# remoteVolume.net
KiCad netlist of a schematic drawn in EAGLE
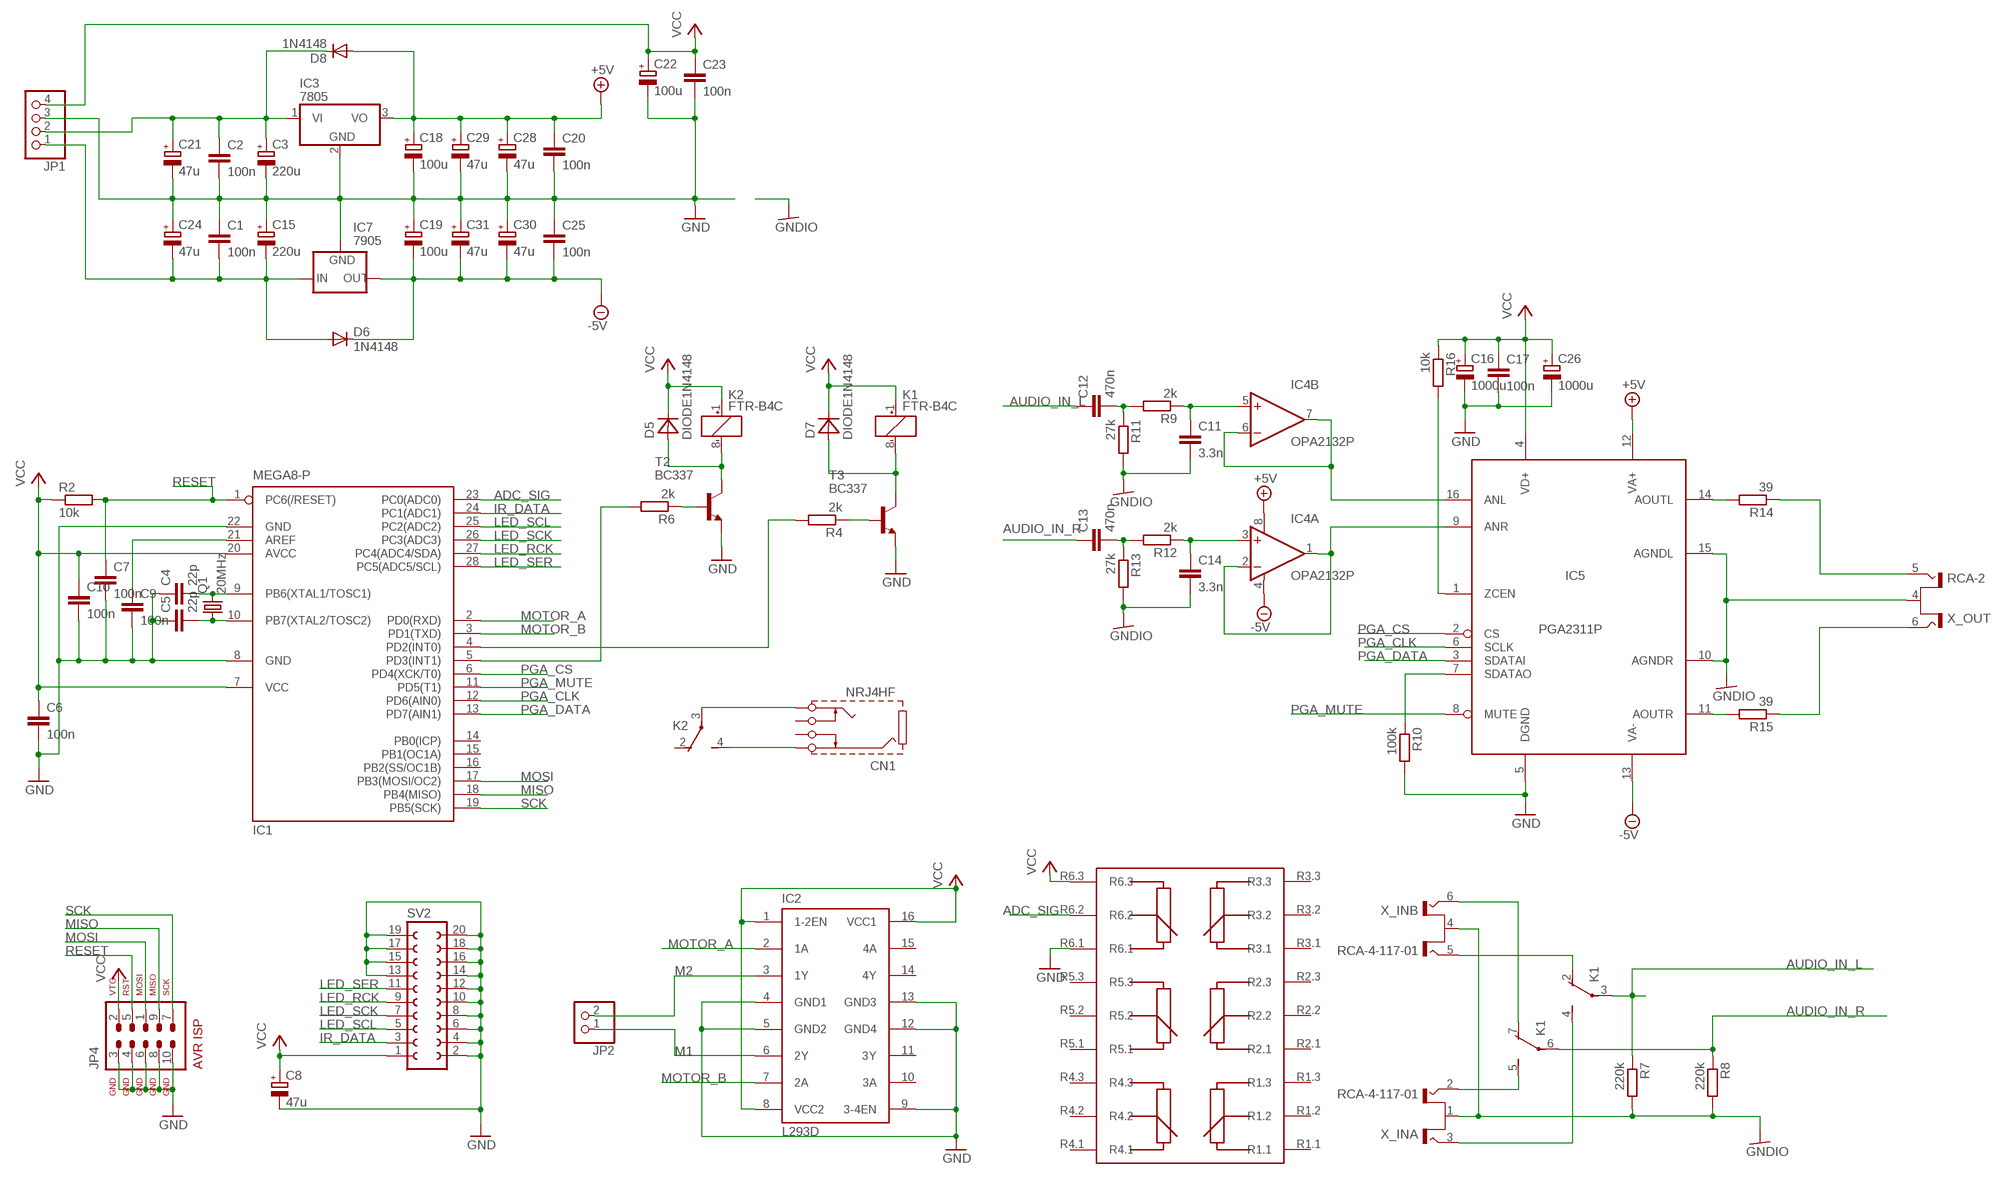
[diagram p0: schematic, sheet 1]

(export (version "E")
  (design (tool "Eeschema 10.0.6"))
  (components
    (comp (ref "C1")
      (value "100n")
      (footprint "eagle-import:C025-025X050")
      (libsource (lib "eagle-import") (part "C-EU025-025X050"))
    )
    (comp (ref "C2")
      (value "100n")
      (footprint "eagle-import:C025-025X050")
      (libsource (lib "eagle-import") (part "C-EU025-025X050"))
    )
    (comp (ref "C3")
      (value "220u")
      (footprint "eagle-import:E2,5-6")
      (libsource (lib "eagle-import") (part "CPOL-EUE2.5-6"))
    )
    (comp (ref "C4")
      (value "22p")
      (footprint "eagle-import:C025-025X050")
      (libsource (lib "eagle-import") (part "C-EU025-025X050"))
    )
    (comp (ref "C5")
      (value "22p")
      (footprint "eagle-import:C025-025X050")
      (libsource (lib "eagle-import") (part "C-EU025-025X050"))
    )
    (comp (ref "C6")
      (value "100n")
      (footprint "eagle-import:C025-025X050")
      (libsource (lib "eagle-import") (part "C-EU025-025X050"))
    )
    (comp (ref "C7")
      (value "100n")
      (footprint "eagle-import:C025-025X050")
      (libsource (lib "eagle-import") (part "C-EU025-025X050"))
    )
    (comp (ref "C8")
      (value "47u")
      (footprint "eagle-import:E2,5-6")
      (libsource (lib "eagle-import") (part "CPOL-EUE2.5-6"))
    )
    (comp (ref "C9")
      (value "100n")
      (footprint "eagle-import:C025-025X050")
      (libsource (lib "eagle-import") (part "C-EU025-025X050"))
    )
    (comp (ref "C10")
      (value "100n")
      (footprint "eagle-import:C025-025X050")
      (libsource (lib "eagle-import") (part "C-EU025-025X050"))
    )
    (comp (ref "C11")
      (value "3.3n")
      (footprint "eagle-import:C050-055X075")
      (libsource (lib "eagle-import") (part "C-EU050-055X075"))
    )
    (comp (ref "C12")
      (value "470n")
      (footprint "eagle-import:C5B3.5")
      (libsource (lib "eagle-import") (part "C5/3.5"))
    )
    (comp (ref "C13")
      (value "470n")
      (footprint "eagle-import:C5B3.5")
      (libsource (lib "eagle-import") (part "C5/3.5"))
    )
    (comp (ref "C14")
      (value "3.3n")
      (footprint "eagle-import:C050-055X075")
      (libsource (lib "eagle-import") (part "C-EU050-055X075"))
    )
    (comp (ref "C15")
      (value "220u")
      (footprint "eagle-import:E2,5-6")
      (libsource (lib "eagle-import") (part "CPOL-EUE2.5-6"))
    )
    (comp (ref "C16")
      (value "1000u")
      (footprint "eagle-import:E3,5-8")
      (libsource (lib "eagle-import") (part "CPOL-EUE3.5-8"))
    )
    (comp (ref "C17")
      (value "100n")
      (footprint "eagle-import:C025-025X050")
      (libsource (lib "eagle-import") (part "C-EU025-025X050"))
    )
    (comp (ref "C18")
      (value "100u")
      (footprint "eagle-import:E2,5-5")
      (libsource (lib "eagle-import") (part "CPOL-EUE2.5-5"))
    )
    (comp (ref "C19")
      (value "100u")
      (footprint "eagle-import:E2,5-5")
      (libsource (lib "eagle-import") (part "CPOL-EUE2.5-5"))
    )
    (comp (ref "C20")
      (value "100n")
      (footprint "eagle-import:C025-025X050")
      (libsource (lib "eagle-import") (part "C-EU025-025X050"))
    )
    (comp (ref "C21")
      (value "47u")
      (footprint "eagle-import:E2,5-5")
      (libsource (lib "eagle-import") (part "CPOL-EUE2.5-5"))
    )
    (comp (ref "C22")
      (value "100u")
      (footprint "eagle-import:E2,5-5")
      (libsource (lib "eagle-import") (part "CPOL-EUE2.5-5"))
    )
    (comp (ref "C23")
      (value "100n")
      (footprint "eagle-import:C025-025X050")
      (libsource (lib "eagle-import") (part "C-EU025-025X050"))
    )
    (comp (ref "C24")
      (value "47u")
      (footprint "eagle-import:E2,5-5")
      (libsource (lib "eagle-import") (part "CPOL-EUE2.5-5"))
    )
    (comp (ref "C25")
      (value "100n")
      (footprint "eagle-import:C025-025X050")
      (libsource (lib "eagle-import") (part "C-EU025-025X050"))
    )
    (comp (ref "C26")
      (value "1000u")
      (footprint "eagle-import:E3,5-8")
      (libsource (lib "eagle-import") (part "CPOL-EUE3.5-8"))
    )
    (comp (ref "C28")
      (value "47u")
      (footprint "eagle-import:E2,5-5")
      (libsource (lib "eagle-import") (part "CPOL-EUE2.5-5"))
    )
    (comp (ref "C29")
      (value "47u")
      (footprint "eagle-import:E2,5-5")
      (libsource (lib "eagle-import") (part "CPOL-EUE2.5-5"))
    )
    (comp (ref "C30")
      (value "47u")
      (footprint "eagle-import:E2,5-5")
      (libsource (lib "eagle-import") (part "CPOL-EUE2.5-5"))
    )
    (comp (ref "C31")
      (value "47u")
      (footprint "eagle-import:E2,5-5")
      (libsource (lib "eagle-import") (part "CPOL-EUE2.5-5"))
    )
    (comp (ref "CN1")
      (value "NRJ4HF")
      (footprint "eagle-import:NRJ4HF")
      (libsource (lib "eagle-import") (part "NRJ4HF"))
    )
    (comp (ref "D5")
      (value "DIODE1N4148")
      (footprint "eagle-import:DO-35")
      (libsource (lib "eagle-import") (part "DIODE1N4148"))
    )
    (comp (ref "D6")
      (value "1N4148")
      (footprint "eagle-import:DO35-7")
      (libsource (lib "eagle-import") (part "1N4148DO35-7"))
    )
    (comp (ref "D7")
      (value "DIODE1N4148")
      (footprint "eagle-import:DO-35")
      (libsource (lib "eagle-import") (part "DIODE1N4148"))
    )
    (comp (ref "D8")
      (value "1N4148")
      (footprint "eagle-import:DO35-7")
      (libsource (lib "eagle-import") (part "1N4148DO35-7"))
    )
    (comp (ref "IC1")
      (value "MEGA8-P")
      (footprint "eagle-import:DIL28-3")
      (libsource (lib "eagle-import") (part "MEGA8-P"))
    )
    (comp (ref "IC2")
      (value "L293D")
      (footprint "eagle-import:DIL16")
      (libsource (lib "eagle-import") (part "L293D"))
    )
    (comp (ref "IC3")
      (value "7805")
      (footprint "eagle-import:TO220V")
      (libsource (lib "eagle-import") (part "78TV05"))
    )
    (comp (ref "IC4")
      (value "OPA2132P")
      (footprint "eagle-import:DIL08")
      (libsource (lib "eagle-import") (part "OPA2132P"))
    )
    (comp (ref "IC5")
      (value "PGA2311P")
      (footprint "eagle-import:DIL16")
      (libsource (lib "eagle-import") (part "PGA2311P"))
    )
    (comp (ref "IC7")
      (value "7905")
      (footprint "eagle-import:79XXS")
      (libsource (lib "eagle-import") (part "79XXS"))
    )
    (comp (ref "JP1")
      (value "PINHD-1X4/90")
      (footprint "eagle-import:1X04_90")
      (libsource (lib "eagle-import") (part "PINHD-1X4/90"))
    )
    (comp (ref "JP2")
      (value "PINHD-1X2")
      (footprint "eagle-import:1X02")
      (libsource (lib "eagle-import") (part "PINHD-1X2"))
    )
    (comp (ref "JP4")
      (value "AVR-ISP-10")
      (footprint "eagle-import:AVR-ISP-10")
      (libsource (lib "eagle-import") (part "AVR-ISP-10"))
    )
    (comp (ref "K1")
      (value "FTR-B4C")
      (footprint "eagle-import:FTR-B4C")
      (libsource (lib "eagle-import") (part "FTR-B4C"))
    )
    (comp (ref "K2")
      (value "FTR-B4C")
      (footprint "eagle-import:FTR-B4C")
      (libsource (lib "eagle-import") (part "FTR-B4C"))
    )
    (comp (ref "Q1")
      (value "20MHz")
      (footprint "eagle-import:HC49_S")
      (libsource (lib "eagle-import") (part "CRYSTALHC49S"))
    )
    (comp (ref "R2")
      (value "10k")
      (footprint "eagle-import:0207_7")
      (libsource (lib "eagle-import") (part "R-EU_0207/7"))
    )
    (comp (ref "R4")
      (value "2k")
      (footprint "eagle-import:0207_7")
      (libsource (lib "eagle-import") (part "R-EU_0207/7"))
    )
    (comp (ref "R6")
      (value "2k")
      (footprint "eagle-import:0207_7")
      (libsource (lib "eagle-import") (part "R-EU_0207/7"))
    )
    (comp (ref "R7")
      (value "220k")
      (footprint "eagle-import:0207_7")
      (libsource (lib "eagle-import") (part "R-EU_0207/7"))
    )
    (comp (ref "R8")
      (value "220k")
      (footprint "eagle-import:0207_7")
      (libsource (lib "eagle-import") (part "R-EU_0207/7"))
    )
    (comp (ref "R9")
      (value "2k")
      (footprint "eagle-import:0207_7")
      (libsource (lib "eagle-import") (part "R-EU_0207/7"))
    )
    (comp (ref "R10")
      (value "100k")
      (footprint "eagle-import:0207_7")
      (libsource (lib "eagle-import") (part "R-EU_0207/7"))
    )
    (comp (ref "R11")
      (value "27k")
      (footprint "eagle-import:0207_7")
      (libsource (lib "eagle-import") (part "R-EU_0207/7"))
    )
    (comp (ref "R12")
      (value "2k")
      (footprint "eagle-import:0207_7")
      (libsource (lib "eagle-import") (part "R-EU_0207/7"))
    )
    (comp (ref "R13")
      (value "27k")
      (footprint "eagle-import:0207_7")
      (libsource (lib "eagle-import") (part "R-EU_0207/7"))
    )
    (comp (ref "R14")
      (value "39")
      (footprint "eagle-import:0207_7")
      (libsource (lib "eagle-import") (part "R-EU_0207/7"))
    )
    (comp (ref "R15")
      (value "39")
      (footprint "eagle-import:0207_7")
      (libsource (lib "eagle-import") (part "R-EU_0207/7"))
    )
    (comp (ref "R16")
      (value "10k")
      (footprint "eagle-import:0207_7")
      (libsource (lib "eagle-import") (part "R-EU_0207/7"))
    )
    (comp (ref "SV2")
      (value "FE10-2W")
      (footprint "eagle-import:FE10-2W")
      (libsource (lib "eagle-import") (part "FE10-2W"))
    )
    (comp (ref "T2")
      (value "BC337")
      (footprint "eagle-import:TO92")
      (libsource (lib "eagle-import") (part "BC337"))
    )
    (comp (ref "T3")
      (value "BC337")
      (footprint "eagle-import:TO92")
      (libsource (lib "eagle-import") (part "BC337"))
    )
    (comp (ref "U$1")
      (value "RK16816MG")
      (footprint "eagle-import:RK16816MG")
      (libsource (lib "eagle-import") (part "RK16816MG"))
    )
    (comp (ref "X_IN")
      (value "RCA-4-117-01")
      (footprint "eagle-import:RCA-4-117-01")
      (libsource (lib "eagle-import") (part "RCA-4-117-01"))
    )
    (comp (ref "X_OUT")
      (value "RCA-2")
      (footprint "eagle-import:RCA-2")
      (libsource (lib "eagle-import") (part "RCA-2"))
    )
  )
  (nets
    (net (code "1") (name "+5V") (class "Default")
      (node (ref "C18") (pin "+") (pinfunction "+_+") (pintype "passive"))
      (node (ref "C20") (pin "1") (pinfunction "1_1") (pintype "passive"))
      (node (ref "C28") (pin "+") (pinfunction "+_+") (pintype "passive"))
      (node (ref "C29") (pin "+") (pinfunction "+_+") (pintype "passive"))
      (node (ref "D8") (pin "A") (pinfunction "A_A") (pintype "passive"))
      (node (ref "IC3") (pin "3") (pinfunction "VO_3") (pintype "passive"))
      (node (ref "IC4") (pin "8") (pinfunction "V+_8") (pintype "power_in"))
      (node (ref "IC5") (pin "12") (pinfunction "VA+_12") (pintype "power_in"))
    )
    (net (code "2") (name "-5V") (class "Default")
      (node (ref "C19") (pin "-") (pinfunction "-_-") (pintype "passive"))
      (node (ref "C25") (pin "2") (pinfunction "2_2") (pintype "passive"))
      (node (ref "C30") (pin "-") (pinfunction "-_-") (pintype "passive"))
      (node (ref "C31") (pin "-") (pinfunction "-_-") (pintype "passive"))
      (node (ref "D6") (pin "C") (pinfunction "C_C") (pintype "passive"))
      (node (ref "IC4") (pin "4") (pinfunction "V-_4") (pintype "power_in"))
      (node (ref "IC5") (pin "13") (pinfunction "VA-_13") (pintype "power_in"))
      (node (ref "IC7") (pin "OUT") (pinfunction "OUT_OUT") (pintype "passive"))
    )
    (net (code "3") (name "/ADC_SIG") (class "Default")
      (node (ref "IC1") (pin "23") (pinfunction "PC0(ADC0)_23") (pintype "bidirectional"))
      (node (ref "U$1") (pin "R6.2") (pinfunction "R6.2_R6.2") (pintype "bidirectional"))
    )
    (net (code "4") (name "/AUDIO_IN_L") (class "Default")
      (node (ref "C12") (pin "1") (pinfunction "1_1") (pintype "passive"))
      (node (ref "K1") (pin "3") (pinfunction "P_3") (pintype "passive"))
      (node (ref "R7") (pin "1") (pinfunction "1_1") (pintype "passive"))
    )
    (net (code "5") (name "/AUDIO_IN_R") (class "Default")
      (node (ref "C13") (pin "1") (pinfunction "1_1") (pintype "passive"))
      (node (ref "K1") (pin "6") (pinfunction "P_6") (pintype "passive"))
      (node (ref "R8") (pin "1") (pinfunction "1_1") (pintype "passive"))
    )
    (net (code "6") (name "/IR_DATA") (class "Default")
      (node (ref "IC1") (pin "24") (pinfunction "PC1(ADC1)_24") (pintype "bidirectional"))
      (node (ref "SV2") (pin "3") (pinfunction "3_3") (pintype "passive"))
    )
    (net (code "7") (name "/LED_RCK") (class "Default")
      (node (ref "IC1") (pin "27") (pinfunction "PC4(ADC4/SDA)_27") (pintype "bidirectional"))
      (node (ref "SV2") (pin "9") (pinfunction "9_9") (pintype "passive"))
    )
    (net (code "8") (name "/LED_SCK") (class "Default")
      (node (ref "IC1") (pin "26") (pinfunction "PC3(ADC3)_26") (pintype "bidirectional"))
      (node (ref "SV2") (pin "7") (pinfunction "7_7") (pintype "passive"))
    )
    (net (code "9") (name "/LED_SCL") (class "Default")
      (node (ref "IC1") (pin "25") (pinfunction "PC2(ADC2)_25") (pintype "bidirectional"))
      (node (ref "SV2") (pin "5") (pinfunction "5_5") (pintype "passive"))
    )
    (net (code "10") (name "/LED_SER") (class "Default")
      (node (ref "IC1") (pin "28") (pinfunction "PC5(ADC5/SCL)_28") (pintype "bidirectional"))
      (node (ref "SV2") (pin "11") (pinfunction "11_11") (pintype "passive"))
    )
    (net (code "11") (name "/M1") (class "Default")
      (node (ref "IC2") (pin "6") (pinfunction "2Y_6") (pintype "output"))
      (node (ref "JP2") (pin "1") (pinfunction "1_1") (pintype "passive"))
    )
    (net (code "12") (name "/M2") (class "Default")
      (node (ref "IC2") (pin "3") (pinfunction "1Y_3") (pintype "output"))
      (node (ref "JP2") (pin "2") (pinfunction "2_2") (pintype "passive"))
    )
    (net (code "13") (name "/MISO") (class "Default")
      (node (ref "IC1") (pin "18") (pinfunction "PB4(MISO)_18") (pintype "bidirectional"))
      (node (ref "JP4") (pin "9") (pinfunction "9_9") (pintype "passive"))
    )
    (net (code "14") (name "/MOSI") (class "Default")
      (node (ref "IC1") (pin "17") (pinfunction "PB3(MOSI/OC2)_17") (pintype "bidirectional"))
      (node (ref "JP4") (pin "1") (pinfunction "1_1") (pintype "passive"))
    )
    (net (code "15") (name "/MOTOR_A") (class "Default")
      (node (ref "IC1") (pin "2") (pinfunction "PD0(RXD)_2") (pintype "bidirectional"))
      (node (ref "IC2") (pin "2") (pinfunction "1A_2") (pintype "input"))
    )
    (net (code "16") (name "/MOTOR_B") (class "Default")
      (node (ref "IC1") (pin "3") (pinfunction "PD1(TXD)_3") (pintype "bidirectional"))
      (node (ref "IC2") (pin "7") (pinfunction "2A_7") (pintype "input"))
    )
    (net (code "17") (name "/PGA_CLK") (class "Default")
      (node (ref "IC1") (pin "12") (pinfunction "PD6(AIN0)_12") (pintype "bidirectional"))
      (node (ref "IC5") (pin "6") (pinfunction "SCLK_6") (pintype "input"))
    )
    (net (code "18") (name "/PGA_CS") (class "Default")
      (node (ref "IC1") (pin "6") (pinfunction "PD4(XCK/T0)_6") (pintype "bidirectional"))
      (node (ref "IC5") (pin "2") (pinfunction "CS_2") (pintype "input"))
    )
    (net (code "19") (name "/PGA_DATA") (class "Default")
      (node (ref "IC1") (pin "13") (pinfunction "PD7(AIN1)_13") (pintype "bidirectional"))
      (node (ref "IC5") (pin "3") (pinfunction "SDATAI_3") (pintype "input"))
    )
    (net (code "20") (name "/PGA_MUTE") (class "Default")
      (node (ref "IC1") (pin "11") (pinfunction "PD5(T1)_11") (pintype "bidirectional"))
      (node (ref "IC5") (pin "8") (pinfunction "MUTE_8") (pintype "input"))
    )
    (net (code "21") (name "/RESET") (class "Default")
      (node (ref "C7") (pin "1") (pinfunction "1_1") (pintype "passive"))
      (node (ref "IC1") (pin "1") (pinfunction "PC6(/RESET)_1") (pintype "bidirectional"))
      (node (ref "JP4") (pin "5") (pinfunction "5_5") (pintype "passive"))
      (node (ref "R2") (pin "2") (pinfunction "2_2") (pintype "passive"))
    )
    (net (code "22") (name "/SCK") (class "Default")
      (node (ref "IC1") (pin "19") (pinfunction "PB5(SCK)_19") (pintype "bidirectional"))
      (node (ref "JP4") (pin "7") (pinfunction "7_7") (pintype "passive"))
    )
    (net (code "23") (name "GND") (class "Default")
      (node (ref "C1") (pin "1") (pinfunction "1_1") (pintype "passive"))
      (node (ref "C10") (pin "2") (pinfunction "2_2") (pintype "passive"))
      (node (ref "C15") (pin "+") (pinfunction "+_+") (pintype "passive"))
      (node (ref "C16") (pin "-") (pinfunction "-_-") (pintype "passive"))
      (node (ref "C17") (pin "2") (pinfunction "2_2") (pintype "passive"))
      (node (ref "C18") (pin "-") (pinfunction "-_-") (pintype "passive"))
      (node (ref "C19") (pin "+") (pinfunction "+_+") (pintype "passive"))
      (node (ref "C2") (pin "2") (pinfunction "2_2") (pintype "passive"))
      (node (ref "C20") (pin "2") (pinfunction "2_2") (pintype "passive"))
      (node (ref "C21") (pin "-") (pinfunction "-_-") (pintype "passive"))
      (node (ref "C22") (pin "-") (pinfunction "-_-") (pintype "passive"))
      (node (ref "C23") (pin "2") (pinfunction "2_2") (pintype "passive"))
      (node (ref "C24") (pin "+") (pinfunction "+_+") (pintype "passive"))
      (node (ref "C25") (pin "1") (pinfunction "1_1") (pintype "passive"))
      (node (ref "C26") (pin "-") (pinfunction "-_-") (pintype "passive"))
      (node (ref "C28") (pin "-") (pinfunction "-_-") (pintype "passive"))
      (node (ref "C29") (pin "-") (pinfunction "-_-") (pintype "passive"))
      (node (ref "C3") (pin "-") (pinfunction "-_-") (pintype "passive"))
      (node (ref "C30") (pin "+") (pinfunction "+_+") (pintype "passive"))
      (node (ref "C31") (pin "+") (pinfunction "+_+") (pintype "passive"))
      (node (ref "C4") (pin "1") (pinfunction "1_1") (pintype "passive"))
      (node (ref "C5") (pin "1") (pinfunction "1_1") (pintype "passive"))
      (node (ref "C6") (pin "2") (pinfunction "2_2") (pintype "passive"))
      (node (ref "C7") (pin "2") (pinfunction "2_2") (pintype "passive"))
      (node (ref "C8") (pin "-") (pinfunction "-_-") (pintype "passive"))
      (node (ref "C9") (pin "2") (pinfunction "2_2") (pintype "passive"))
      (node (ref "IC1") (pin "22") (pinfunction "GND_22") (pintype "power_in"))
      (node (ref "IC1") (pin "8") (pinfunction "GND_8") (pintype "power_in"))
      (node (ref "IC2") (pin "12") (pinfunction "GND4_12") (pintype "power_in"))
      (node (ref "IC2") (pin "13") (pinfunction "GND3_13") (pintype "power_in"))
      (node (ref "IC2") (pin "4") (pinfunction "GND1_4") (pintype "power_in"))
      (node (ref "IC2") (pin "5") (pinfunction "GND2_5") (pintype "power_in"))
      (node (ref "IC2") (pin "9") (pinfunction "3-4EN_9") (pintype "input"))
      (node (ref "IC3") (pin "2") (pinfunction "GND_2") (pintype "passive"))
      (node (ref "IC5") (pin "5") (pinfunction "DGND_5") (pintype "power_in"))
      (node (ref "IC7") (pin "GND") (pinfunction "GND_GND") (pintype "input"))
      (node (ref "JP1") (pin "3") (pinfunction "3_3") (pintype "passive"))
      (node (ref "JP4") (pin "10") (pinfunction "10_10") (pintype "passive"))
      (node (ref "JP4") (pin "3") (pinfunction "3_3") (pintype "passive"))
      (node (ref "JP4") (pin "4") (pinfunction "4_4") (pintype "passive"))
      (node (ref "JP4") (pin "6") (pinfunction "6_6") (pintype "passive"))
      (node (ref "JP4") (pin "8") (pinfunction "8_8") (pintype "passive"))
      (node (ref "R10") (pin "2") (pinfunction "2_2") (pintype "passive"))
      (node (ref "SV2") (pin "10") (pinfunction "10_10") (pintype "passive"))
      (node (ref "SV2") (pin "12") (pinfunction "12_12") (pintype "passive"))
      (node (ref "SV2") (pin "13") (pinfunction "13_13") (pintype "passive"))
      (node (ref "SV2") (pin "14") (pinfunction "14_14") (pintype "passive"))
      (node (ref "SV2") (pin "15") (pinfunction "15_15") (pintype "passive"))
      (node (ref "SV2") (pin "16") (pinfunction "16_16") (pintype "passive"))
      (node (ref "SV2") (pin "17") (pinfunction "17_17") (pintype "passive"))
      (node (ref "SV2") (pin "18") (pinfunction "18_18") (pintype "passive"))
      (node (ref "SV2") (pin "19") (pinfunction "19_19") (pintype "passive"))
      (node (ref "SV2") (pin "2") (pinfunction "2_2") (pintype "passive"))
      (node (ref "SV2") (pin "20") (pinfunction "20_20") (pintype "passive"))
      (node (ref "SV2") (pin "4") (pinfunction "4_4") (pintype "passive"))
      (node (ref "SV2") (pin "6") (pinfunction "6_6") (pintype "passive"))
      (node (ref "SV2") (pin "8") (pinfunction "8_8") (pintype "passive"))
      (node (ref "T2") (pin "1") (pinfunction "E_1") (pintype "passive"))
      (node (ref "T3") (pin "1") (pinfunction "E_1") (pintype "passive"))
      (node (ref "U$1") (pin "R6.1") (pinfunction "R6.1_R6.1") (pintype "bidirectional"))
    )
    (net (code "24") (name "GNDIO") (class "Default")
      (node (ref "C11") (pin "2") (pinfunction "2_2") (pintype "passive"))
      (node (ref "C14") (pin "2") (pinfunction "2_2") (pintype "passive"))
      (node (ref "IC5") (pin "10") (pinfunction "AGNDR_10") (pintype "power_in"))
      (node (ref "IC5") (pin "15") (pinfunction "AGNDL_15") (pintype "power_in"))
      (node (ref "R11") (pin "2") (pinfunction "2_2") (pintype "passive"))
      (node (ref "R13") (pin "2") (pinfunction "2_2") (pintype "passive"))
      (node (ref "R7") (pin "2") (pinfunction "2_2") (pintype "passive"))
      (node (ref "R8") (pin "2") (pinfunction "2_2") (pintype "passive"))
      (node (ref "X_IN") (pin "1") (pinfunction "S_1") (pintype "passive"))
      (node (ref "X_IN") (pin "4") (pinfunction "S_4") (pintype "passive"))
      (node (ref "X_OUT") (pin "4") (pinfunction "S_4") (pintype "passive"))
    )
    (net (code "25") (name "Net-(C1-Pad2)") (class "Default")
      (node (ref "C1") (pin "2") (pinfunction "2_2") (pintype "passive"))
      (node (ref "C15") (pin "-") (pinfunction "-_-") (pintype "passive"))
      (node (ref "C24") (pin "-") (pinfunction "-_-") (pintype "passive"))
      (node (ref "D6") (pin "A") (pinfunction "A_A") (pintype "passive"))
      (node (ref "IC7") (pin "IN") (pinfunction "IN_IN") (pintype "input"))
      (node (ref "JP1") (pin "1") (pinfunction "1_1") (pintype "passive"))
    )
    (net (code "26") (name "Net-(C12-Pad2)") (class "Default")
      (node (ref "C12") (pin "2") (pinfunction "2_2") (pintype "passive"))
      (node (ref "R11") (pin "1") (pinfunction "1_1") (pintype "passive"))
      (node (ref "R9") (pin "2") (pinfunction "2_2") (pintype "passive"))
    )
    (net (code "27") (name "Net-(C13-Pad2)") (class "Default")
      (node (ref "C13") (pin "2") (pinfunction "2_2") (pintype "passive"))
      (node (ref "R12") (pin "2") (pinfunction "2_2") (pintype "passive"))
      (node (ref "R13") (pin "1") (pinfunction "1_1") (pintype "passive"))
    )
    (net (code "28") (name "Net-(IC1-AREF)") (class "Default")
      (node (ref "C9") (pin "1") (pinfunction "1_1") (pintype "passive"))
      (node (ref "IC1") (pin "21") (pinfunction "AREF_21") (pintype "passive"))
    )
    (net (code "29") (name "Net-(IC1-PB6(XTAL1{slash}TOSC1))") (class "Default")
      (node (ref "C4") (pin "2") (pinfunction "2_2") (pintype "passive"))
      (node (ref "IC1") (pin "9") (pinfunction "PB6(XTAL1/TOSC1)_9") (pintype "bidirectional"))
      (node (ref "Q1") (pin "2") (pinfunction "2_2") (pintype "passive"))
    )
    (net (code "30") (name "Net-(IC1-PB7(XTAL2{slash}TOSC2))") (class "Default")
      (node (ref "C5") (pin "2") (pinfunction "2_2") (pintype "passive"))
      (node (ref "IC1") (pin "10") (pinfunction "PB7(XTAL2/TOSC2)_10") (pintype "bidirectional"))
      (node (ref "Q1") (pin "1") (pinfunction "1_1") (pintype "passive"))
    )
    (net (code "31") (name "Net-(IC1-PD2(INT0))") (class "Default")
      (node (ref "IC1") (pin "4") (pinfunction "PD2(INT0)_4") (pintype "bidirectional"))
      (node (ref "R4") (pin "2") (pinfunction "2_2") (pintype "passive"))
    )
    (net (code "32") (name "Net-(IC1-PD3(INT1))") (class "Default")
      (node (ref "IC1") (pin "5") (pinfunction "PD3(INT1)_5") (pintype "bidirectional"))
      (node (ref "R6") (pin "2") (pinfunction "2_2") (pintype "passive"))
    )
    (net (code "33") (name "Net-(IC3-VI)") (class "Default")
      (node (ref "C2") (pin "1") (pinfunction "1_1") (pintype "passive"))
      (node (ref "C21") (pin "+") (pinfunction "+_+") (pintype "passive"))
      (node (ref "C3") (pin "+") (pinfunction "+_+") (pintype "passive"))
      (node (ref "D8") (pin "C") (pinfunction "C_C") (pintype "passive"))
      (node (ref "IC3") (pin "1") (pinfunction "VI_1") (pintype "input"))
      (node (ref "JP1") (pin "2") (pinfunction "2_2") (pintype "passive"))
    )
    (net (code "34") (name "Net-(IC4A-+IN)") (class "Default")
      (node (ref "C14") (pin "1") (pinfunction "1_1") (pintype "passive"))
      (node (ref "IC4") (pin "3") (pinfunction "+IN_3") (pintype "input"))
      (node (ref "R12") (pin "1") (pinfunction "1_1") (pintype "passive"))
    )
    (net (code "35") (name "Net-(IC4A--IN)") (class "Default")
      (node (ref "IC4") (pin "1") (pinfunction "OUT_1") (pintype "output"))
      (node (ref "IC4") (pin "2") (pinfunction "-IN_2") (pintype "input"))
      (node (ref "IC5") (pin "9") (pinfunction "ANR_9") (pintype "input"))
    )
    (net (code "36") (name "Net-(IC4B-+IN)") (class "Default")
      (node (ref "C11") (pin "1") (pinfunction "1_1") (pintype "passive"))
      (node (ref "IC4") (pin "5") (pinfunction "+IN_5") (pintype "input"))
      (node (ref "R9") (pin "1") (pinfunction "1_1") (pintype "passive"))
    )
    (net (code "37") (name "Net-(IC4B--IN)") (class "Default")
      (node (ref "IC4") (pin "6") (pinfunction "-IN_6") (pintype "input"))
      (node (ref "IC4") (pin "7") (pinfunction "OUT_7") (pintype "output"))
      (node (ref "IC5") (pin "16") (pinfunction "ANL_16") (pintype "input"))
    )
    (net (code "38") (name "Net-(IC5-AOUTL)") (class "Default")
      (node (ref "IC5") (pin "14") (pinfunction "AOUTL_14") (pintype "output"))
      (node (ref "R14") (pin "2") (pinfunction "2_2") (pintype "passive"))
    )
    (net (code "39") (name "Net-(IC5-AOUTR)") (class "Default")
      (node (ref "IC5") (pin "11") (pinfunction "AOUTR_11") (pintype "output"))
      (node (ref "R15") (pin "2") (pinfunction "2_2") (pintype "passive"))
    )
    (net (code "40") (name "Net-(IC5-SDATAO)") (class "Default")
      (node (ref "IC5") (pin "7") (pinfunction "SDATAO_7") (pintype "output"))
      (node (ref "R10") (pin "1") (pinfunction "1_1") (pintype "passive"))
    )
    (net (code "41") (name "Net-(IC5-ZCEN)") (class "Default")
      (node (ref "IC5") (pin "1") (pinfunction "ZCEN_1") (pintype "input"))
      (node (ref "R16") (pin "2") (pinfunction "2_2") (pintype "passive"))
    )
    (net (code "42") (name "Net-(K1A-O)") (class "Default")
      (node (ref "K1") (pin "2") (pinfunction "O_2") (pintype "passive"))
      (node (ref "X_IN") (pin "5") (pinfunction "T1_5") (pintype "passive"))
    )
    (net (code "43") (name "Net-(K1A-S)") (class "Default")
      (node (ref "K1") (pin "4") (pinfunction "S_4") (pintype "passive"))
      (node (ref "X_IN") (pin "3") (pinfunction "T2_3") (pintype "passive"))
    )
    (net (code "44") (name "Net-(K1B-O)") (class "Default")
      (node (ref "K1") (pin "7") (pinfunction "O_7") (pintype "passive"))
      (node (ref "X_IN") (pin "6") (pinfunction "T2_6") (pintype "passive"))
    )
    (net (code "45") (name "Net-(K1B-S)") (class "Default")
      (node (ref "K1") (pin "5") (pinfunction "S_5") (pintype "passive"))
      (node (ref "X_IN") (pin "2") (pinfunction "T1_2") (pintype "passive"))
    )
    (net (code "46") (name "Net-(K1C--)") (class "Default")
      (node (ref "D7") (pin "+") (pinfunction "+_+") (pintype "passive"))
      (node (ref "K1") (pin "8") (pinfunction "-_8") (pintype "passive"))
      (node (ref "T3") (pin "3") (pinfunction "C_3") (pintype "passive"))
    )
    (net (code "47") (name "Net-(K2A-P)") (class "Default")
      (node (ref "CN1") (pin "TIP") (pinfunction "TIP_TIP") (pintype "passive"))
      (node (ref "K2") (pin "3") (pinfunction "P_3") (pintype "passive"))
    )
    (net (code "48") (name "Net-(K2A-S)") (class "Default")
      (node (ref "CN1") (pin "SLEEVE") (pinfunction "SLEEVE_SLEEVE") (pintype "passive"))
      (node (ref "K2") (pin "4") (pinfunction "S_4") (pintype "passive"))
    )
    (net (code "49") (name "Net-(K2C--)") (class "Default")
      (node (ref "D5") (pin "+") (pinfunction "+_+") (pintype "passive"))
      (node (ref "K2") (pin "8") (pinfunction "-_8") (pintype "passive"))
      (node (ref "T2") (pin "3") (pinfunction "C_3") (pintype "passive"))
    )
    (net (code "50") (name "Net-(T2-B)") (class "Default")
      (node (ref "R6") (pin "1") (pinfunction "1_1") (pintype "passive"))
      (node (ref "T2") (pin "2") (pinfunction "B_2") (pintype "passive"))
    )
    (net (code "51") (name "Net-(T3-B)") (class "Default")
      (node (ref "R4") (pin "1") (pinfunction "1_1") (pintype "passive"))
      (node (ref "T3") (pin "2") (pinfunction "B_2") (pintype "passive"))
    )
    (net (code "52") (name "Net-(X_OUT-T1)") (class "Default")
      (node (ref "R14") (pin "1") (pinfunction "1_1") (pintype "passive"))
      (node (ref "X_OUT") (pin "5") (pinfunction "T1_5") (pintype "passive"))
    )
    (net (code "53") (name "Net-(X_OUT-T2)") (class "Default")
      (node (ref "R15") (pin "1") (pinfunction "1_1") (pintype "passive"))
      (node (ref "X_OUT") (pin "6") (pinfunction "T2_6") (pintype "passive"))
    )
    (net (code "54") (name "VCC") (class "Default")
      (node (ref "C10") (pin "1") (pinfunction "1_1") (pintype "passive"))
      (node (ref "C16") (pin "+") (pinfunction "+_+") (pintype "passive"))
      (node (ref "C17") (pin "1") (pinfunction "1_1") (pintype "passive"))
      (node (ref "C22") (pin "+") (pinfunction "+_+") (pintype "passive"))
      (node (ref "C23") (pin "1") (pinfunction "1_1") (pintype "passive"))
      (node (ref "C26") (pin "+") (pinfunction "+_+") (pintype "passive"))
      (node (ref "C6") (pin "1") (pinfunction "1_1") (pintype "passive"))
      (node (ref "C8") (pin "+") (pinfunction "+_+") (pintype "passive"))
      (node (ref "D5") (pin "-") (pinfunction "-_-") (pintype "passive"))
      (node (ref "D7") (pin "-") (pinfunction "-_-") (pintype "passive"))
      (node (ref "IC1") (pin "20") (pinfunction "AVCC_20") (pintype "power_in"))
      (node (ref "IC1") (pin "7") (pinfunction "VCC_7") (pintype "power_in"))
      (node (ref "IC2") (pin "1") (pinfunction "1-2EN_1") (pintype "input"))
      (node (ref "IC2") (pin "16") (pinfunction "VCC1_16") (pintype "power_in"))
      (node (ref "IC2") (pin "8") (pinfunction "VCC2_8") (pintype "power_in"))
      (node (ref "IC5") (pin "4") (pinfunction "VD+_4") (pintype "power_in"))
      (node (ref "JP1") (pin "4") (pinfunction "4_4") (pintype "passive"))
      (node (ref "JP4") (pin "2") (pinfunction "2_2") (pintype "passive"))
      (node (ref "K1") (pin "1") (pinfunction "+_1") (pintype "passive"))
      (node (ref "K2") (pin "1") (pinfunction "+_1") (pintype "passive"))
      (node (ref "R16") (pin "1") (pinfunction "1_1") (pintype "passive"))
      (node (ref "R2") (pin "1") (pinfunction "1_1") (pintype "passive"))
      (node (ref "SV2") (pin "1") (pinfunction "1_1") (pintype "passive"))
      (node (ref "U$1") (pin "R6.3") (pinfunction "R6.3_R6.3") (pintype "bidirectional"))
    )
    (net (code "55") (name "unconnected-(CN1-PadSLEEVE-S)") (class "Default")
      (node (ref "CN1") (pin "SLEEVE-S") (pinfunction "SLEEVE-S_SLEEVE-S") (pintype "passive"))
    )
    (net (code "56") (name "unconnected-(CN1-PadTIP-S)") (class "Default")
      (node (ref "CN1") (pin "TIP-S") (pinfunction "TIP-S_TIP-S") (pintype "passive"))
    )
    (net (code "57") (name "unconnected-(IC1-PB0(ICP)-Pad14)") (class "Default")
      (node (ref "IC1") (pin "14") (pinfunction "PB0(ICP)_14") (pintype "bidirectional"))
    )
    (net (code "58") (name "unconnected-(IC1-PB1(OC1A)-Pad15)") (class "Default")
      (node (ref "IC1") (pin "15") (pinfunction "PB1(OC1A)_15") (pintype "bidirectional"))
    )
    (net (code "59") (name "unconnected-(IC1-PB2(SS{slash}OC1B)-Pad16)") (class "Default")
      (node (ref "IC1") (pin "16") (pinfunction "PB2(SS/OC1B)_16") (pintype "bidirectional"))
    )
    (net (code "60") (name "unconnected-(IC2-3A-Pad10)") (class "Default")
      (node (ref "IC2") (pin "10") (pinfunction "3A_10") (pintype "input"))
    )
    (net (code "61") (name "unconnected-(IC2-3Y-Pad11)") (class "Default")
      (node (ref "IC2") (pin "11") (pinfunction "3Y_11") (pintype "output"))
    )
    (net (code "62") (name "unconnected-(IC2-4A-Pad15)") (class "Default")
      (node (ref "IC2") (pin "15") (pinfunction "4A_15") (pintype "input"))
    )
    (net (code "63") (name "unconnected-(IC2-4Y-Pad14)") (class "Default")
      (node (ref "IC2") (pin "14") (pinfunction "4Y_14") (pintype "output"))
    )
    (net (code "64") (name "unconnected-(K2A-O-Pad2)") (class "Default")
      (node (ref "K2") (pin "2") (pinfunction "O_2") (pintype "passive"))
    )
    (net (code "65") (name "unconnected-(U$1-PadR1.1)") (class "Default")
      (node (ref "U$1") (pin "R1.1") (pinfunction "R1.1_R1.1") (pintype "bidirectional"))
    )
    (net (code "66") (name "unconnected-(U$1-PadR1.2)") (class "Default")
      (node (ref "U$1") (pin "R1.2") (pinfunction "R1.2_R1.2") (pintype "bidirectional"))
    )
    (net (code "67") (name "unconnected-(U$1-PadR1.3)") (class "Default")
      (node (ref "U$1") (pin "R1.3") (pinfunction "R1.3_R1.3") (pintype "bidirectional"))
    )
    (net (code "68") (name "unconnected-(U$1-PadR2.1)") (class "Default")
      (node (ref "U$1") (pin "R2.1") (pinfunction "R2.1_R2.1") (pintype "bidirectional"))
    )
    (net (code "69") (name "unconnected-(U$1-PadR2.2)") (class "Default")
      (node (ref "U$1") (pin "R2.2") (pinfunction "R2.2_R2.2") (pintype "bidirectional"))
    )
    (net (code "70") (name "unconnected-(U$1-PadR2.3)") (class "Default")
      (node (ref "U$1") (pin "R2.3") (pinfunction "R2.3_R2.3") (pintype "bidirectional"))
    )
    (net (code "71") (name "unconnected-(U$1-PadR3.1)") (class "Default")
      (node (ref "U$1") (pin "R3.1") (pinfunction "R3.1_R3.1") (pintype "bidirectional"))
    )
    (net (code "72") (name "unconnected-(U$1-PadR3.2)") (class "Default")
      (node (ref "U$1") (pin "R3.2") (pinfunction "R3.2_R3.2") (pintype "bidirectional"))
    )
    (net (code "73") (name "unconnected-(U$1-PadR3.3)") (class "Default")
      (node (ref "U$1") (pin "R3.3") (pinfunction "R3.3_R3.3") (pintype "bidirectional"))
    )
    (net (code "74") (name "unconnected-(U$1-PadR4.1)") (class "Default")
      (node (ref "U$1") (pin "R4.1") (pinfunction "R4.1_R4.1") (pintype "bidirectional"))
    )
    (net (code "75") (name "unconnected-(U$1-PadR4.2)") (class "Default")
      (node (ref "U$1") (pin "R4.2") (pinfunction "R4.2_R4.2") (pintype "bidirectional"))
    )
    (net (code "76") (name "unconnected-(U$1-PadR4.3)") (class "Default")
      (node (ref "U$1") (pin "R4.3") (pinfunction "R4.3_R4.3") (pintype "bidirectional"))
    )
    (net (code "77") (name "unconnected-(U$1-PadR5.1)") (class "Default")
      (node (ref "U$1") (pin "R5.1") (pinfunction "R5.1_R5.1") (pintype "bidirectional"))
    )
    (net (code "78") (name "unconnected-(U$1-PadR5.2)") (class "Default")
      (node (ref "U$1") (pin "R5.2") (pinfunction "R5.2_R5.2") (pintype "bidirectional"))
    )
    (net (code "79") (name "unconnected-(U$1-PadR5.3)") (class "Default")
      (node (ref "U$1") (pin "R5.3") (pinfunction "R5.3_R5.3") (pintype "bidirectional"))
    )
  )
)
